# motorBoard.net
KiCad netlist of a schematic drawn in EAGLE
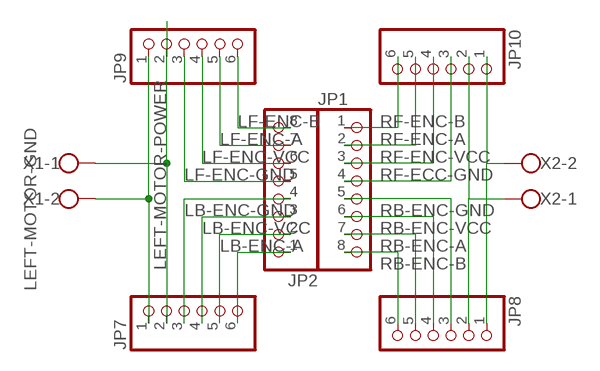
[diagram p0: schematic, sheet 1]

(export (version "E")
  (design (tool "Eeschema 10.0.6"))
  (components
    (comp (ref "JP1")
      (value "PINHD-1X8")
      (footprint "eagle-import:1X08")
      (libsource (lib "eagle-import") (part "PINHD-1X8"))
    )
    (comp (ref "JP2")
      (value "PINHD-1X8")
      (footprint "eagle-import:1X08")
      (libsource (lib "eagle-import") (part "PINHD-1X8"))
    )
    (comp (ref "JP7")
      (value "PINHD-1X6")
      (footprint "eagle-import:1X06")
      (libsource (lib "eagle-import") (part "PINHD-1X6"))
    )
    (comp (ref "JP8")
      (value "PINHD-1X6")
      (footprint "eagle-import:1X06")
      (libsource (lib "eagle-import") (part "PINHD-1X6"))
    )
    (comp (ref "JP9")
      (value "PINHD-1X6")
      (footprint "eagle-import:1X06")
      (libsource (lib "eagle-import") (part "PINHD-1X6"))
    )
    (comp (ref "JP10")
      (value "PINHD-1X6")
      (footprint "eagle-import:1X06")
      (libsource (lib "eagle-import") (part "PINHD-1X6"))
    )
    (comp (ref "X1")
      (value "W237-102")
      (footprint "eagle-import:W237-102")
      (fields (field (name "MPN") "237-102"))
      (libsource (lib "eagle-import") (part "W237-102"))
    )
    (comp (ref "X2")
      (value "W237-102")
      (footprint "eagle-import:W237-102")
      (fields (field (name "MPN") "237-102"))
      (libsource (lib "eagle-import") (part "W237-102"))
    )
  )
  (nets
    (net (code "1") (name "/LB-ENC-A") (class "Default")
      (node (ref "JP2") (pin "2") (pinfunction "2_2") (pintype "passive"))
      (node (ref "JP7") (pin "5") (pinfunction "5_5") (pintype "passive"))
    )
    (net (code "2") (name "/LB-ENC-GND") (class "Default")
      (node (ref "JP2") (pin "4") (pinfunction "4_4") (pintype "passive"))
      (node (ref "JP7") (pin "3") (pinfunction "3_3") (pintype "passive"))
    )
    (net (code "3") (name "/LB-ENC-VCC") (class "Default")
      (node (ref "JP2") (pin "3") (pinfunction "3_3") (pintype "passive"))
      (node (ref "JP7") (pin "4") (pinfunction "4_4") (pintype "passive"))
    )
    (net (code "4") (name "/LEFT-MOTOR-GND") (class "Default")
      (node (ref "JP7") (pin "2") (pinfunction "2_2") (pintype "passive"))
      (node (ref "JP9") (pin "2") (pinfunction "2_2") (pintype "passive"))
      (node (ref "X1") (pin "1") (pinfunction "KL_1") (pintype "passive"))
    )
    (net (code "5") (name "/LEFT-MOTOR-POWER") (class "Default")
      (node (ref "JP7") (pin "1") (pinfunction "1_1") (pintype "passive"))
      (node (ref "JP9") (pin "1") (pinfunction "1_1") (pintype "passive"))
      (node (ref "X1") (pin "2") (pinfunction "KL_2") (pintype "passive"))
    )
    (net (code "6") (name "/LF-ENC-A") (class "Default")
      (node (ref "JP2") (pin "7") (pinfunction "7_7") (pintype "passive"))
      (node (ref "JP9") (pin "5") (pinfunction "5_5") (pintype "passive"))
    )
    (net (code "7") (name "/LF-ENC-B") (class "Default")
      (node (ref "JP2") (pin "8") (pinfunction "8_8") (pintype "passive"))
      (node (ref "JP9") (pin "6") (pinfunction "6_6") (pintype "passive"))
    )
    (net (code "8") (name "/LF-ENC-GND") (class "Default")
      (node (ref "JP2") (pin "5") (pinfunction "5_5") (pintype "passive"))
      (node (ref "JP9") (pin "3") (pinfunction "3_3") (pintype "passive"))
    )
    (net (code "9") (name "/LF-ENC-VCC") (class "Default")
      (node (ref "JP2") (pin "6") (pinfunction "6_6") (pintype "passive"))
      (node (ref "JP9") (pin "4") (pinfunction "4_4") (pintype "passive"))
    )
    (net (code "10") (name "/RB-ENC-A") (class "Default")
      (node (ref "JP1") (pin "7") (pinfunction "7_7") (pintype "passive"))
      (node (ref "JP8") (pin "5") (pinfunction "5_5") (pintype "passive"))
    )
    (net (code "11") (name "/RB-ENC-B") (class "Default")
      (node (ref "JP1") (pin "8") (pinfunction "8_8") (pintype "passive"))
      (node (ref "JP8") (pin "6") (pinfunction "6_6") (pintype "passive"))
    )
    (net (code "12") (name "/RB-ENC-GND") (class "Default")
      (node (ref "JP1") (pin "5") (pinfunction "5_5") (pintype "passive"))
      (node (ref "JP8") (pin "3") (pinfunction "3_3") (pintype "passive"))
    )
    (net (code "13") (name "/RB-ENC-VCC") (class "Default")
      (node (ref "JP1") (pin "6") (pinfunction "6_6") (pintype "passive"))
      (node (ref "JP8") (pin "4") (pinfunction "4_4") (pintype "passive"))
    )
    (net (code "14") (name "/RF-ECC-GND") (class "Default")
      (node (ref "JP1") (pin "4") (pinfunction "4_4") (pintype "passive"))
      (node (ref "JP10") (pin "3") (pinfunction "3_3") (pintype "passive"))
    )
    (net (code "15") (name "/RF-ENC-A") (class "Default")
      (node (ref "JP1") (pin "2") (pinfunction "2_2") (pintype "passive"))
      (node (ref "JP10") (pin "5") (pinfunction "5_5") (pintype "passive"))
    )
    (net (code "16") (name "/RF-ENC-B") (class "Default")
      (node (ref "JP1") (pin "1") (pinfunction "1_1") (pintype "passive"))
      (node (ref "JP10") (pin "6") (pinfunction "6_6") (pintype "passive"))
    )
    (net (code "17") (name "/RF-ENC-VCC") (class "Default")
      (node (ref "JP1") (pin "3") (pinfunction "3_3") (pintype "passive"))
      (node (ref "JP10") (pin "4") (pinfunction "4_4") (pintype "passive"))
    )
    (net (code "18") (name "Net-(JP2-Pad1)") (class "Default")
      (node (ref "JP2") (pin "1") (pinfunction "1_1") (pintype "passive"))
      (node (ref "JP7") (pin "6") (pinfunction "6_6") (pintype "passive"))
    )
    (net (code "19") (name "Net-(X2A-KL)") (class "Default")
      (node (ref "JP10") (pin "2") (pinfunction "2_2") (pintype "passive"))
      (node (ref "JP8") (pin "2") (pinfunction "2_2") (pintype "passive"))
      (node (ref "X2") (pin "1") (pinfunction "KL_1") (pintype "passive"))
    )
    (net (code "20") (name "Net-(X2B-KL)") (class "Default")
      (node (ref "JP10") (pin "1") (pinfunction "1_1") (pintype "passive"))
      (node (ref "JP8") (pin "1") (pinfunction "1_1") (pintype "passive"))
      (node (ref "X2") (pin "2") (pinfunction "KL_2") (pintype "passive"))
    )
  )
)
